# EIT_Recorder.net
KiCad netlist of a schematic drawn in EAGLE
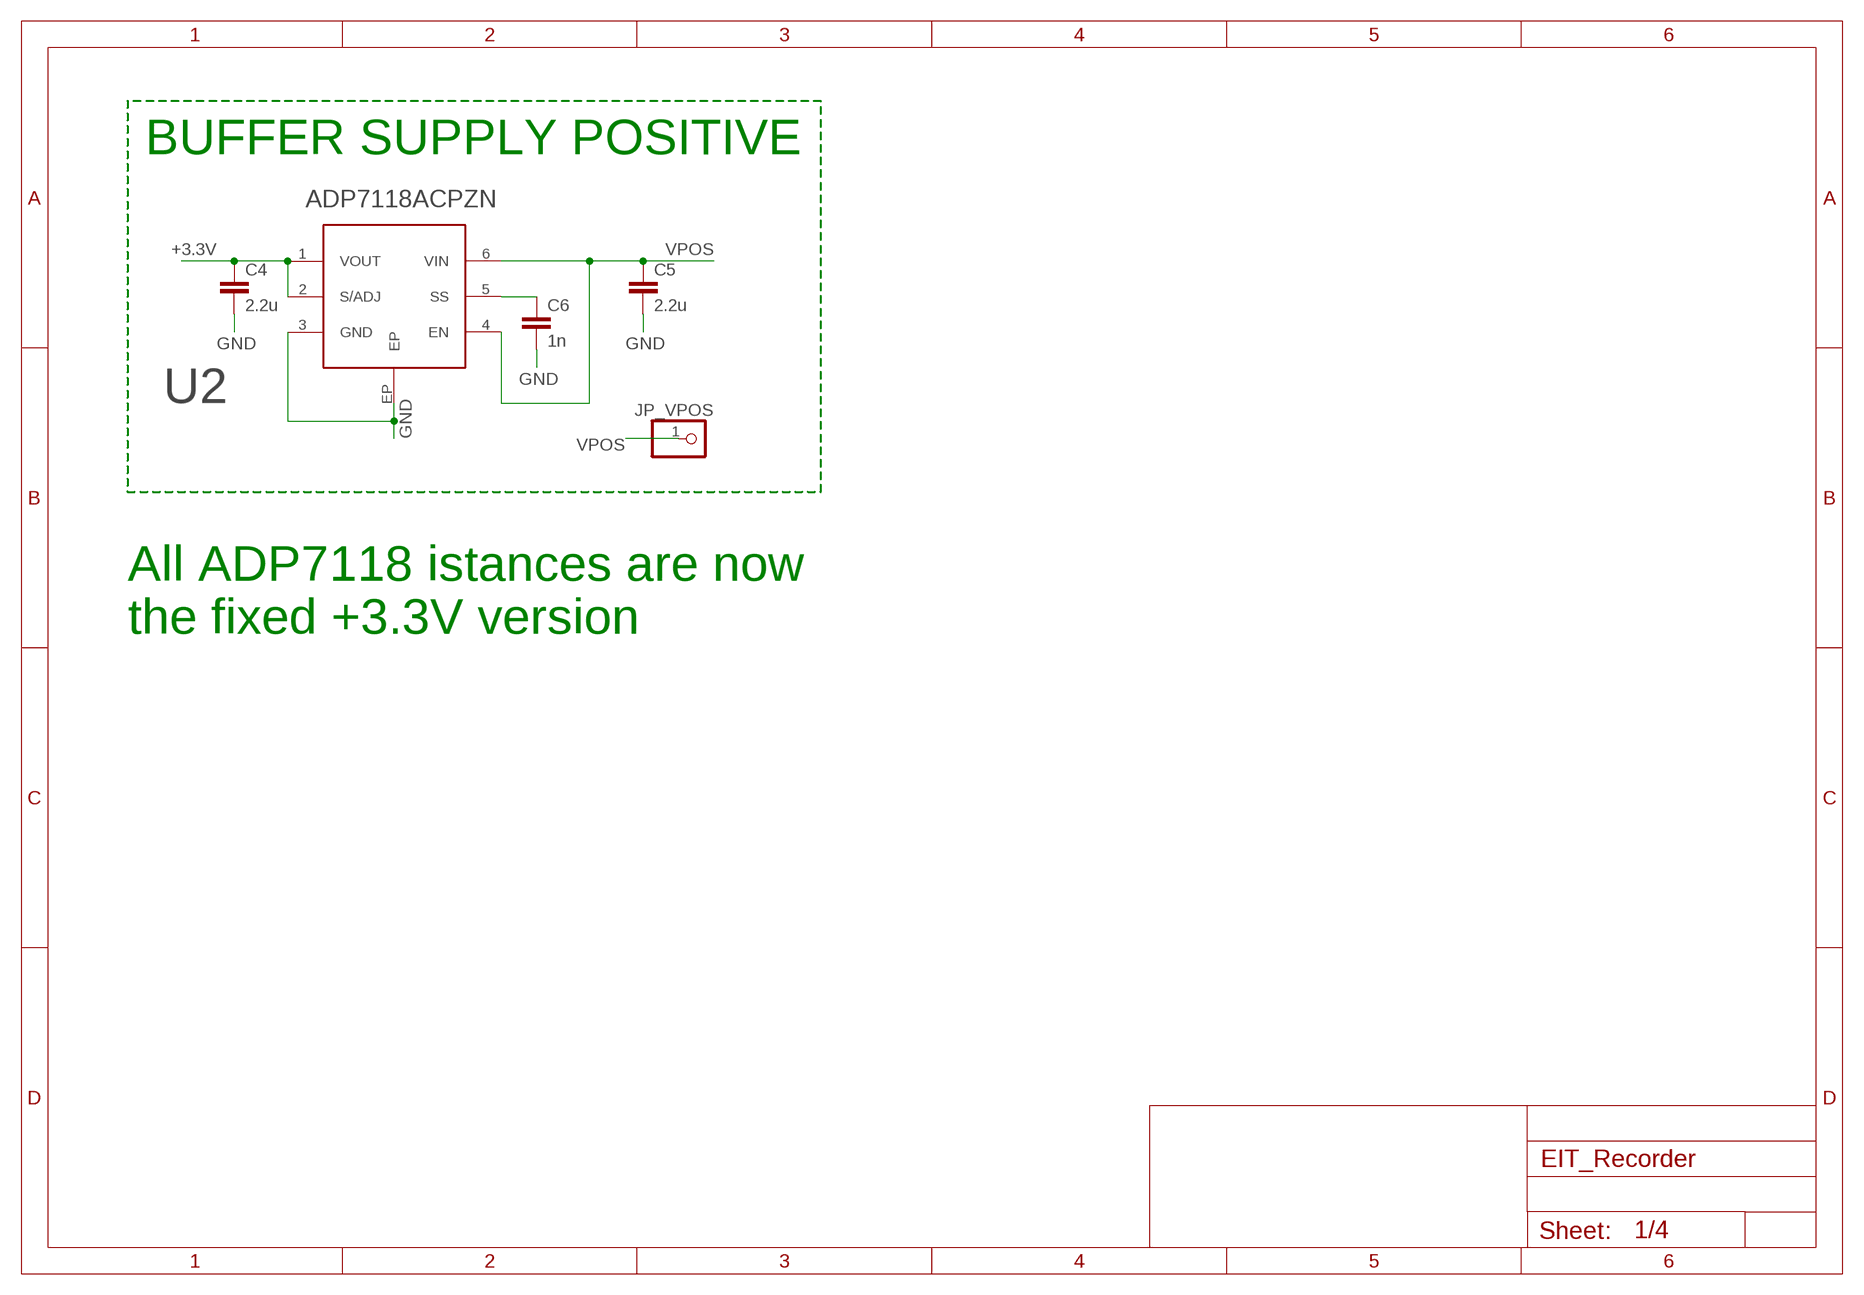
[diagram p0: schematic, sheet 1]
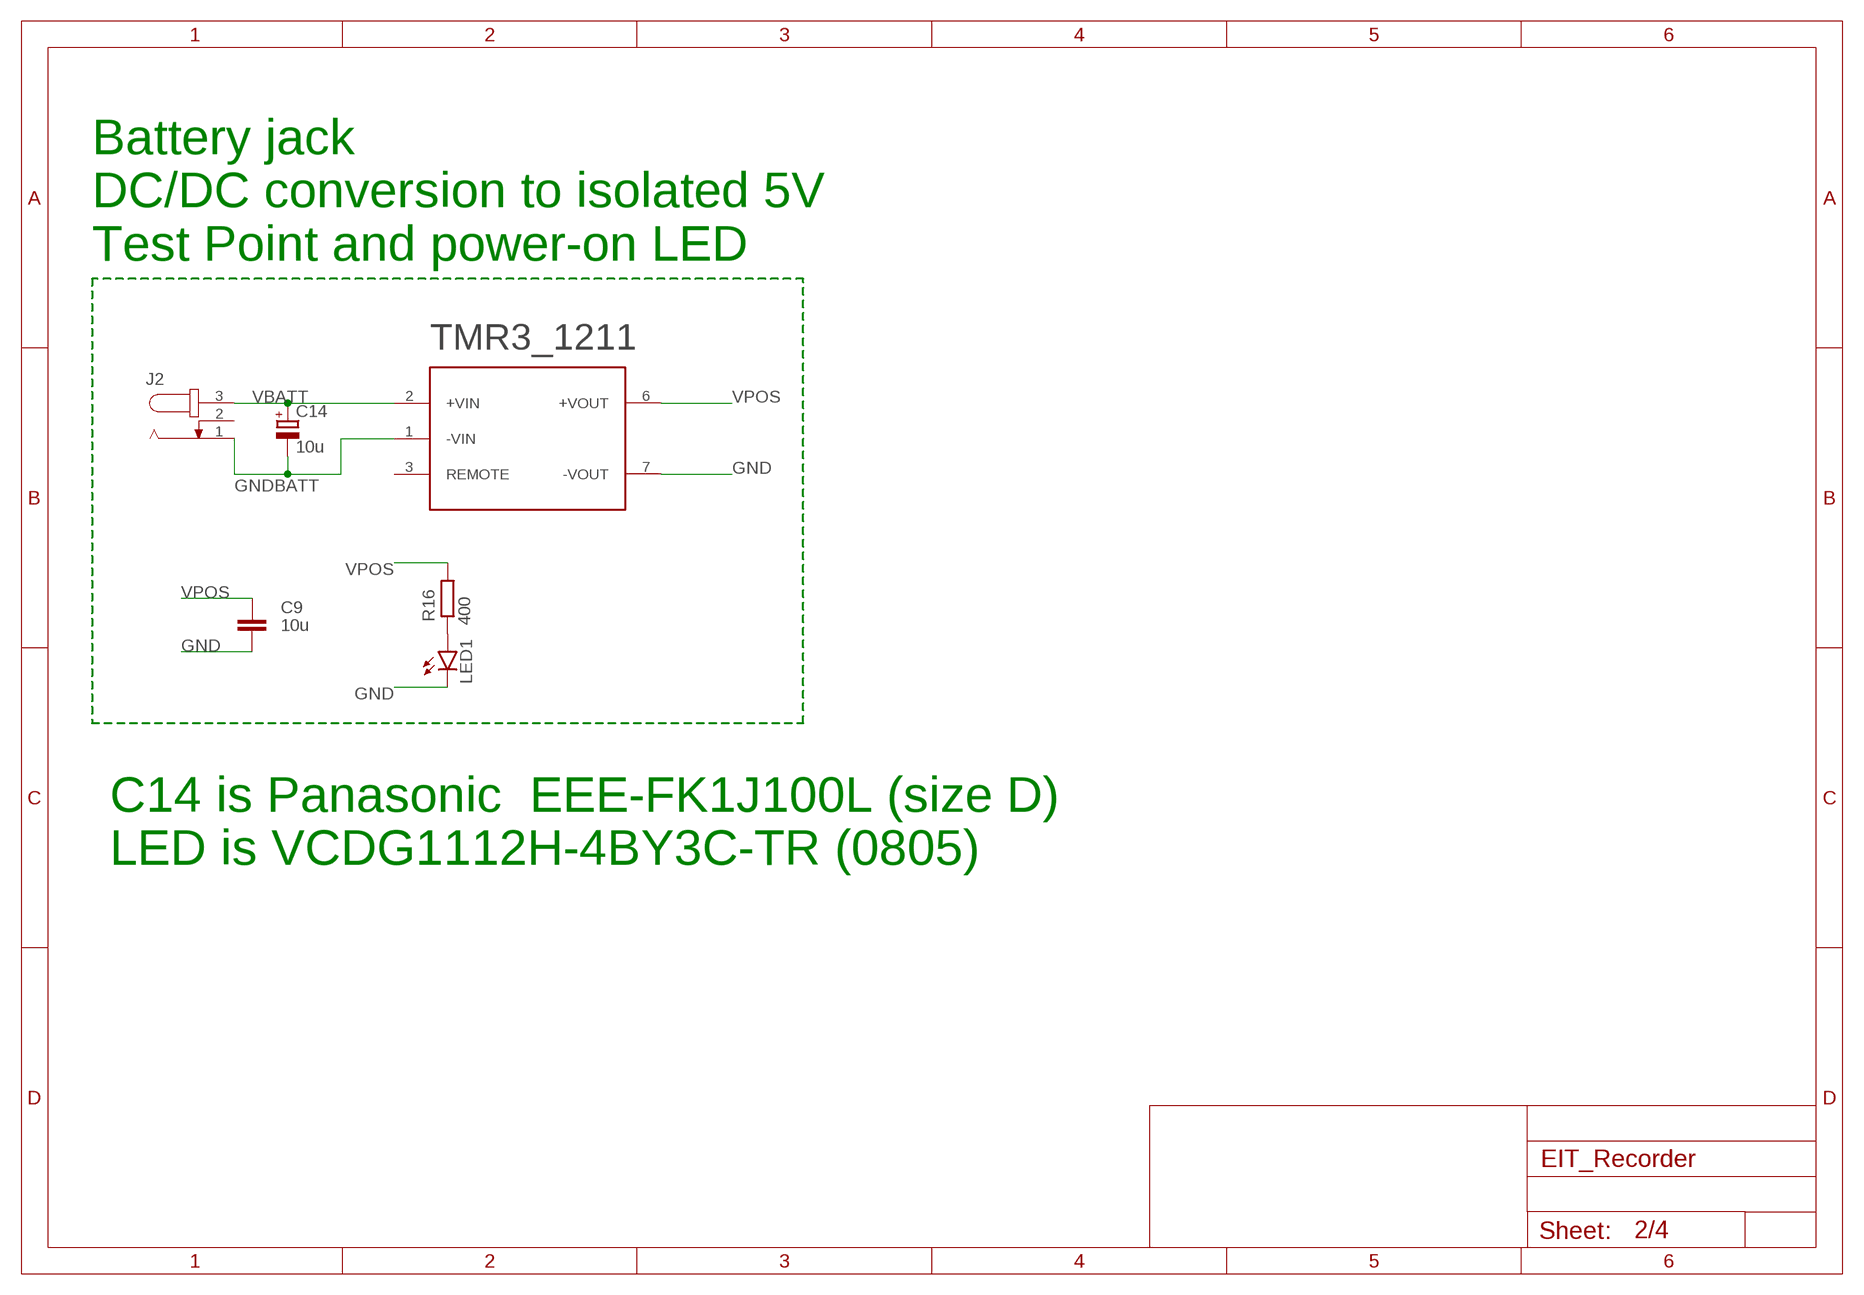
[diagram p1: schematic, sheet 2]
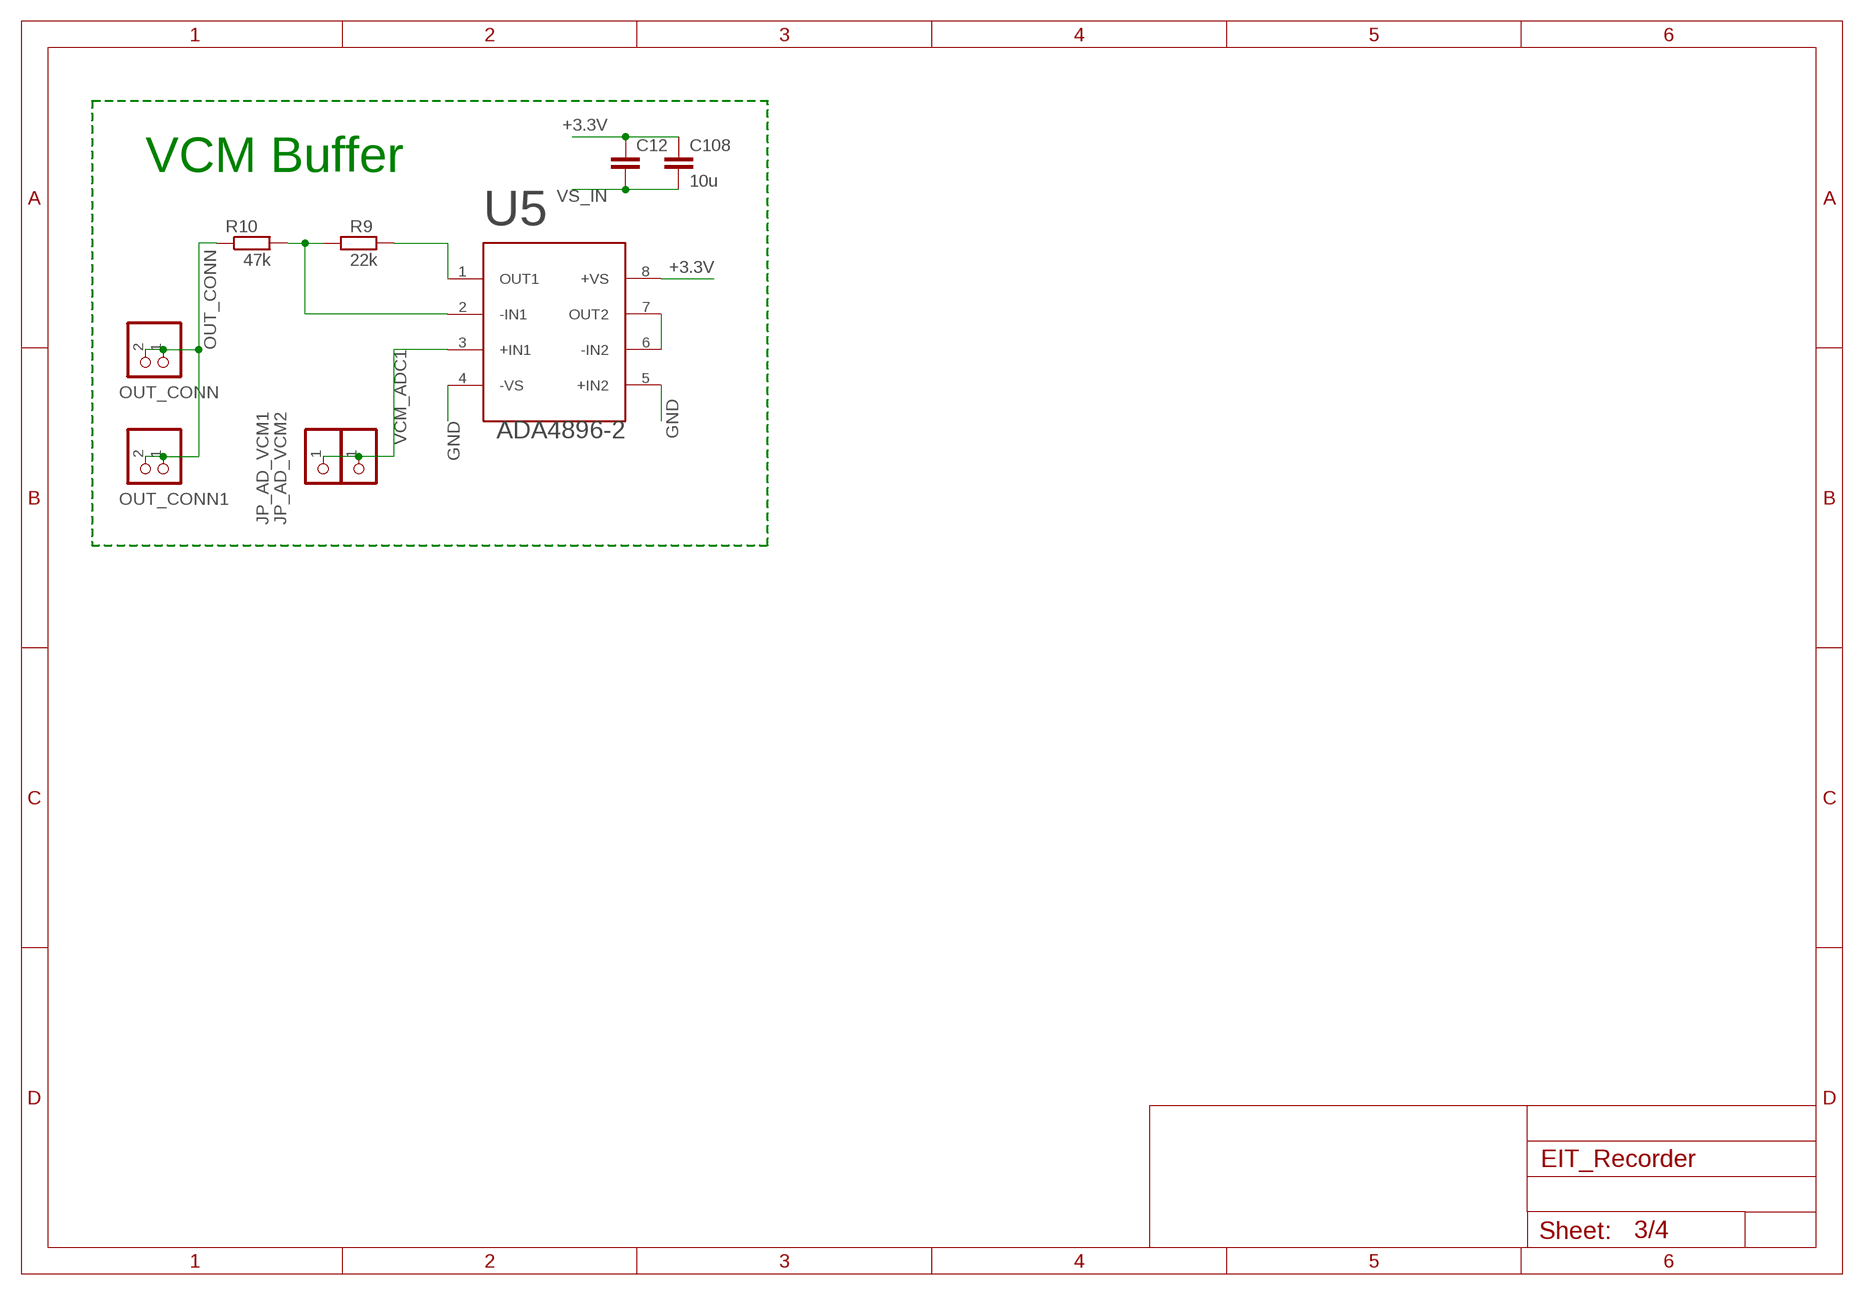
[diagram p2: schematic, sheet 3]
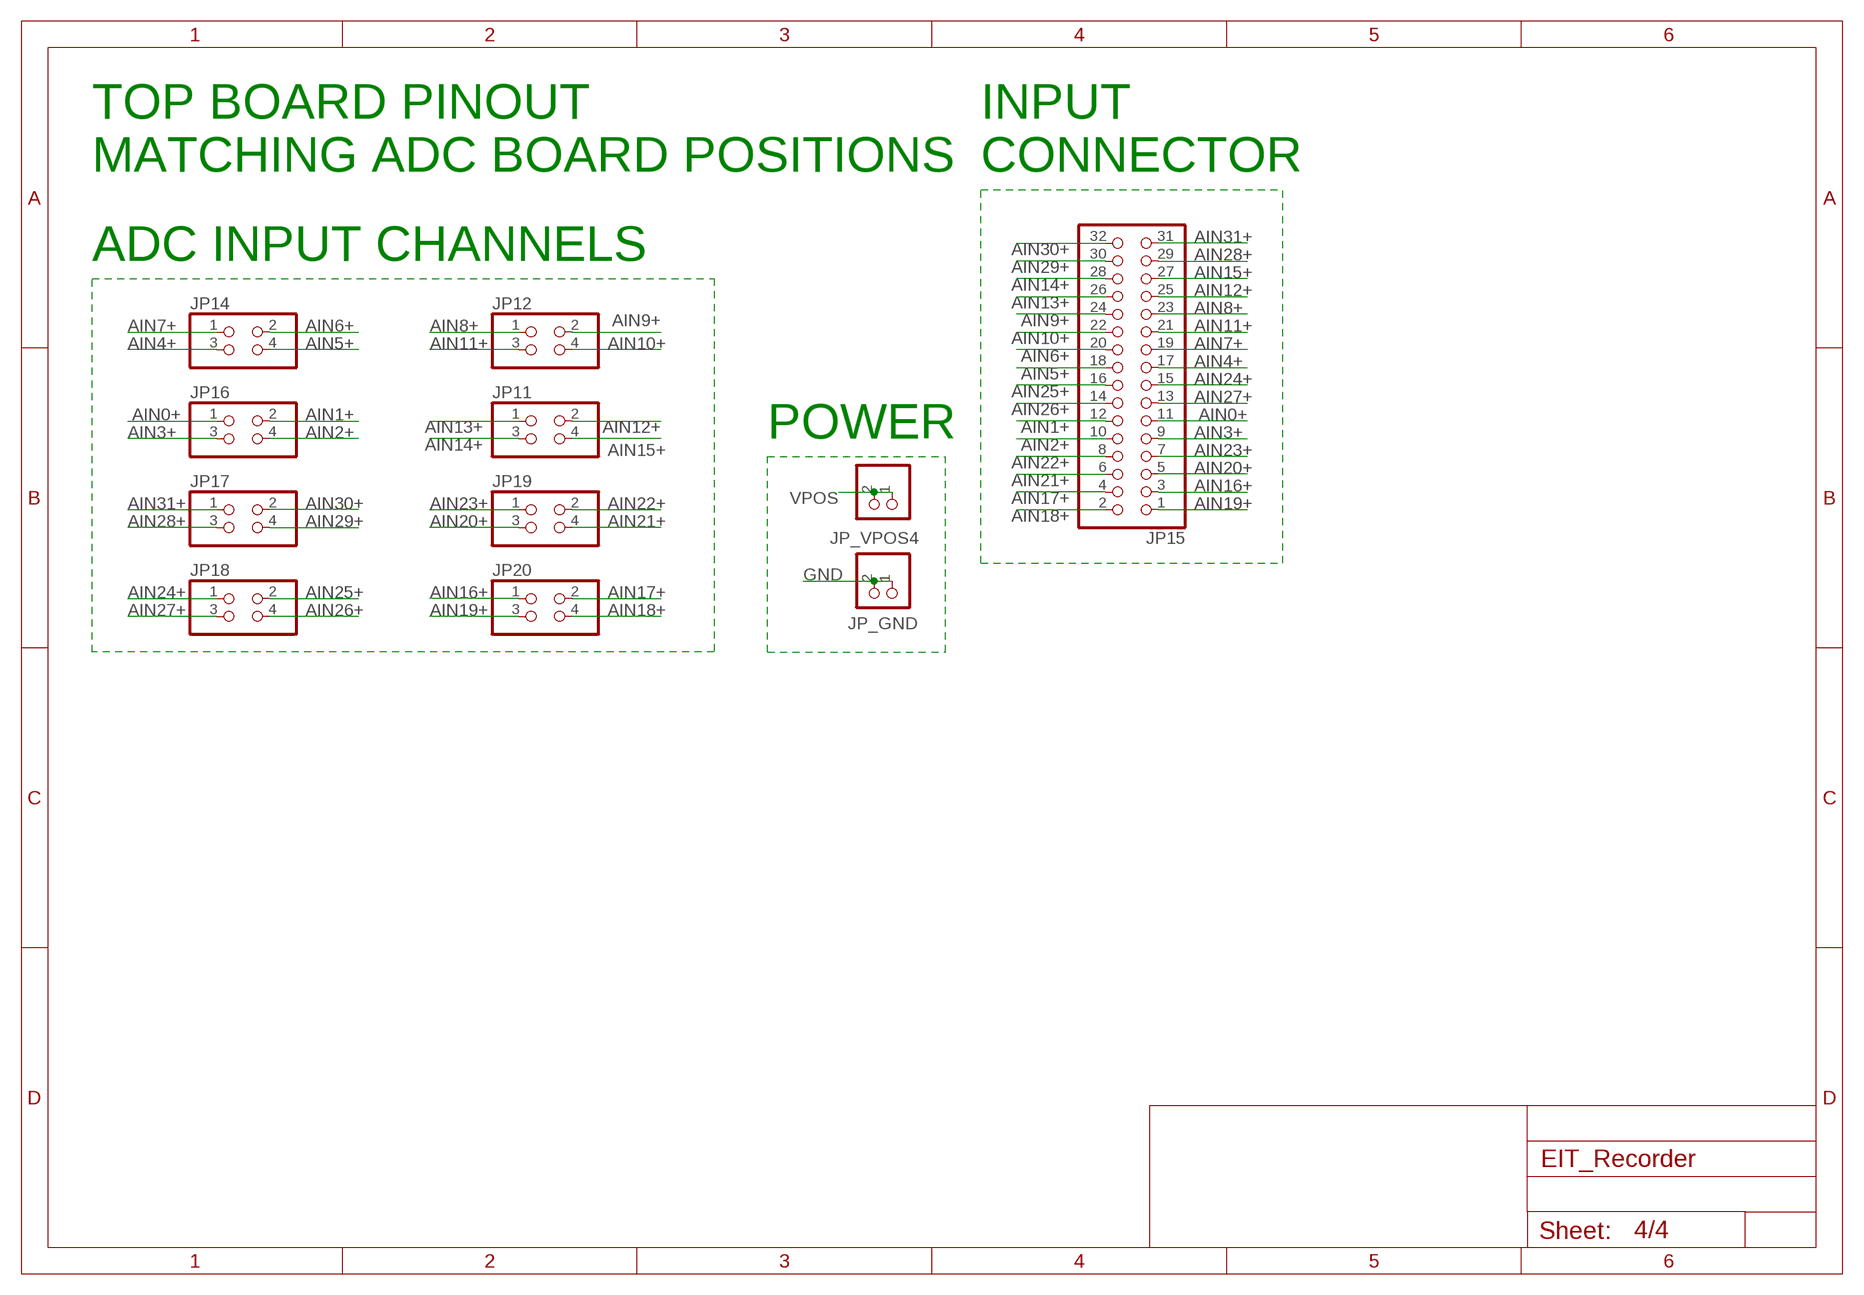
[diagram p3: schematic, sheet 4]

(export (version "E")
  (design (tool "Eeschema 10.0.6"))
  (components
    (comp (ref "C9")
      (value "10u")
      (footprint "eagle-import:C0805")
      (libsource (lib "eagle-import") (part "C0805"))
    )
    (comp (ref "C14")
      (value "10u")
      (footprint "eagle-import:PANASONIC_D")
      (libsource (lib "eagle-import") (part "CPOL-EUD"))
    )
    (comp (ref "J2")
      (value "JACK-PLUG0")
      (footprint "eagle-import:SPC4077")
      (libsource (lib "eagle-import") (part "JACK-PLUG0"))
    )
    (comp (ref "LED1")
      (value "LEDCHIP-LED0805")
      (footprint "eagle-import:CHIP-LED0805")
      (libsource (lib "eagle-import") (part "LEDCHIP-LED0805"))
    )
    (comp (ref "R16")
      (value "400")
      (footprint "eagle-import:R0805")
      (libsource (lib "eagle-import") (part "R-EU_R0805"))
    )
    (comp (ref "TMR3_1211")
      (value "TMR3_1211")
      (footprint "eagle-import:TMR3_1211")
      (libsource (lib "eagle-import") (part "TMR3_1211"))
    )
    (comp (ref "C12")
      (value "0.1u")
      (footprint "eagle-import:C0402")
      (libsource (lib "eagle-import") (part "C0402"))
    )
    (comp (ref "C108")
      (value "10u")
      (footprint "eagle-import:C0805")
      (libsource (lib "eagle-import") (part "C0805"))
    )
    (comp (ref "JP_AD_VCM1")
      (value "PINHD-1X1")
      (footprint "eagle-import:1X01")
      (libsource (lib "eagle-import") (part "PINHD-1X1"))
    )
    (comp (ref "JP_AD_VCM2")
      (value "PINHD-1X1")
      (footprint "eagle-import:1X01")
      (libsource (lib "eagle-import") (part "PINHD-1X1"))
    )
    (comp (ref "OUT_CONN")
      (value "PINHD-1X2")
      (footprint "eagle-import:1X02")
      (libsource (lib "eagle-import") (part "PINHD-1X2"))
    )
    (comp (ref "OUT_CONN1")
      (value "PINHD-1X2")
      (footprint "eagle-import:1X02")
      (libsource (lib "eagle-import") (part "PINHD-1X2"))
    )
    (comp (ref "R9")
      (value "22k")
      (footprint "eagle-import:R0603")
      (libsource (lib "eagle-import") (part "R0603"))
    )
    (comp (ref "R10")
      (value "47k")
      (footprint "eagle-import:R0603")
      (libsource (lib "eagle-import") (part "R0603"))
    )
    (comp (ref "U5")
      (value "ADA4896-2")
      (footprint "eagle-import:MSOP8_CUSTOM")
      (libsource (lib "eagle-import") (part "ADA4896-2"))
    )
    (comp (ref "JP11")
      (value "PINHD-2X2")
      (footprint "eagle-import:2X02")
      (libsource (lib "eagle-import") (part "PINHD-2X2"))
    )
    (comp (ref "JP12")
      (value "PINHD-2X2")
      (footprint "eagle-import:2X02")
      (libsource (lib "eagle-import") (part "PINHD-2X2"))
    )
    (comp (ref "JP14")
      (value "PINHD-2X2")
      (footprint "eagle-import:2X02")
      (libsource (lib "eagle-import") (part "PINHD-2X2"))
    )
    (comp (ref "JP15")
      (value "PINHD-2X16")
      (footprint "eagle-import:2X16")
      (libsource (lib "eagle-import") (part "PINHD-2X16"))
    )
    (comp (ref "JP16")
      (value "PINHD-2X2")
      (footprint "eagle-import:2X02")
      (libsource (lib "eagle-import") (part "PINHD-2X2"))
    )
    (comp (ref "JP17")
      (value "PINHD-2X2")
      (footprint "eagle-import:2X02")
      (libsource (lib "eagle-import") (part "PINHD-2X2"))
    )
    (comp (ref "JP18")
      (value "PINHD-2X2")
      (footprint "eagle-import:2X02")
      (libsource (lib "eagle-import") (part "PINHD-2X2"))
    )
    (comp (ref "JP19")
      (value "PINHD-2X2")
      (footprint "eagle-import:2X02")
      (libsource (lib "eagle-import") (part "PINHD-2X2"))
    )
    (comp (ref "JP20")
      (value "PINHD-2X2")
      (footprint "eagle-import:2X02")
      (libsource (lib "eagle-import") (part "PINHD-2X2"))
    )
    (comp (ref "JP_GND")
      (value "PINHD-1X2")
      (footprint "eagle-import:1X02")
      (libsource (lib "eagle-import") (part "PINHD-1X2"))
    )
    (comp (ref "JP_VPOS4")
      (value "PINHD-1X2")
      (footprint "eagle-import:1X02")
      (libsource (lib "eagle-import") (part "PINHD-1X2"))
    )
    (comp (ref "C4")
      (value "2.2u")
      (footprint "eagle-import:C0603")
      (libsource (lib "eagle-import") (part "C0603"))
    )
    (comp (ref "C5")
      (value "2.2u")
      (footprint "eagle-import:C0603")
      (libsource (lib "eagle-import") (part "C0603"))
    )
    (comp (ref "C6")
      (value "1n")
      (footprint "eagle-import:C0402")
      (libsource (lib "eagle-import") (part "C0402"))
    )
    (comp (ref "JP_VPOS")
      (value "PINHD-1X1")
      (footprint "eagle-import:1X01")
      (libsource (lib "eagle-import") (part "PINHD-1X1"))
    )
    (comp (ref "U2")
      (value "ADP7118ACPZN")
      (footprint "eagle-import:LFCSP6_CUSTOM")
      (libsource (lib "eagle-import") (part "ADP7118ACPZN"))
    )
  )
  (nets
    (net (code "1") (name "+3.3V") (class "Default")
      (node (ref "C108") (pin "1") (pinfunction "1_1") (pintype "passive"))
      (node (ref "C12") (pin "1") (pinfunction "1_1") (pintype "passive"))
      (node (ref "C4") (pin "1") (pinfunction "1_1") (pintype "passive"))
      (node (ref "U2") (pin "1") (pinfunction "VOUT_1") (pintype "power_in"))
      (node (ref "U2") (pin "2") (pinfunction "S/ADJ_2") (pintype "bidirectional"))
      (node (ref "U5") (pin "8") (pinfunction "+VS_8") (pintype "power_in"))
    )
    (net (code "2") (name "AIN0+") (class "Default")
      (node (ref "JP15") (pin "11") (pinfunction "11_11") (pintype "passive"))
      (node (ref "JP16") (pin "1") (pinfunction "1_1") (pintype "passive"))
    )
    (net (code "3") (name "AIN1+") (class "Default")
      (node (ref "JP15") (pin "12") (pinfunction "12_12") (pintype "passive"))
      (node (ref "JP16") (pin "2") (pinfunction "2_2") (pintype "passive"))
    )
    (net (code "4") (name "AIN2+") (class "Default")
      (node (ref "JP15") (pin "10") (pinfunction "10_10") (pintype "passive"))
      (node (ref "JP16") (pin "4") (pinfunction "4_4") (pintype "passive"))
    )
    (net (code "5") (name "AIN3+") (class "Default")
      (node (ref "JP15") (pin "9") (pinfunction "9_9") (pintype "passive"))
      (node (ref "JP16") (pin "3") (pinfunction "3_3") (pintype "passive"))
    )
    (net (code "6") (name "AIN4+") (class "Default")
      (node (ref "JP14") (pin "3") (pinfunction "3_3") (pintype "passive"))
      (node (ref "JP15") (pin "17") (pinfunction "17_17") (pintype "passive"))
    )
    (net (code "7") (name "AIN5+") (class "Default")
      (node (ref "JP14") (pin "4") (pinfunction "4_4") (pintype "passive"))
      (node (ref "JP15") (pin "18") (pinfunction "18_18") (pintype "passive"))
    )
    (net (code "8") (name "AIN6+") (class "Default")
      (node (ref "JP14") (pin "2") (pinfunction "2_2") (pintype "passive"))
      (node (ref "JP15") (pin "20") (pinfunction "20_20") (pintype "passive"))
    )
    (net (code "9") (name "AIN7+") (class "Default")
      (node (ref "JP14") (pin "1") (pinfunction "1_1") (pintype "passive"))
      (node (ref "JP15") (pin "19") (pinfunction "19_19") (pintype "passive"))
    )
    (net (code "10") (name "AIN8+") (class "Default")
      (node (ref "JP12") (pin "1") (pinfunction "1_1") (pintype "passive"))
      (node (ref "JP15") (pin "23") (pinfunction "23_23") (pintype "passive"))
    )
    (net (code "11") (name "AIN9+") (class "Default")
      (node (ref "JP12") (pin "2") (pinfunction "2_2") (pintype "passive"))
      (node (ref "JP15") (pin "24") (pinfunction "24_24") (pintype "passive"))
    )
    (net (code "12") (name "AIN10+") (class "Default")
      (node (ref "JP12") (pin "4") (pinfunction "4_4") (pintype "passive"))
      (node (ref "JP15") (pin "22") (pinfunction "22_22") (pintype "passive"))
    )
    (net (code "13") (name "AIN11+") (class "Default")
      (node (ref "JP12") (pin "3") (pinfunction "3_3") (pintype "passive"))
      (node (ref "JP15") (pin "21") (pinfunction "21_21") (pintype "passive"))
    )
    (net (code "14") (name "AIN12+") (class "Default")
      (node (ref "JP11") (pin "2") (pinfunction "2_2") (pintype "passive"))
      (node (ref "JP15") (pin "25") (pinfunction "25_25") (pintype "passive"))
    )
    (net (code "15") (name "AIN13+") (class "Default")
      (node (ref "JP11") (pin "1") (pinfunction "1_1") (pintype "passive"))
      (node (ref "JP15") (pin "26") (pinfunction "26_26") (pintype "passive"))
    )
    (net (code "16") (name "AIN14+") (class "Default")
      (node (ref "JP11") (pin "3") (pinfunction "3_3") (pintype "passive"))
      (node (ref "JP15") (pin "28") (pinfunction "28_28") (pintype "passive"))
    )
    (net (code "17") (name "AIN15+") (class "Default")
      (node (ref "JP11") (pin "4") (pinfunction "4_4") (pintype "passive"))
      (node (ref "JP15") (pin "27") (pinfunction "27_27") (pintype "passive"))
    )
    (net (code "18") (name "AIN16+") (class "Default")
      (node (ref "JP15") (pin "3") (pinfunction "3_3") (pintype "passive"))
      (node (ref "JP20") (pin "1") (pinfunction "1_1") (pintype "passive"))
    )
    (net (code "19") (name "AIN17+") (class "Default")
      (node (ref "JP15") (pin "4") (pinfunction "4_4") (pintype "passive"))
      (node (ref "JP20") (pin "2") (pinfunction "2_2") (pintype "passive"))
    )
    (net (code "20") (name "AIN18+") (class "Default")
      (node (ref "JP15") (pin "2") (pinfunction "2_2") (pintype "passive"))
      (node (ref "JP20") (pin "4") (pinfunction "4_4") (pintype "passive"))
    )
    (net (code "21") (name "AIN19+") (class "Default")
      (node (ref "JP15") (pin "1") (pinfunction "1_1") (pintype "passive"))
      (node (ref "JP20") (pin "3") (pinfunction "3_3") (pintype "passive"))
    )
    (net (code "22") (name "AIN20+") (class "Default")
      (node (ref "JP15") (pin "5") (pinfunction "5_5") (pintype "passive"))
      (node (ref "JP19") (pin "3") (pinfunction "3_3") (pintype "passive"))
    )
    (net (code "23") (name "AIN21+") (class "Default")
      (node (ref "JP15") (pin "6") (pinfunction "6_6") (pintype "passive"))
      (node (ref "JP19") (pin "4") (pinfunction "4_4") (pintype "passive"))
    )
    (net (code "24") (name "AIN22+") (class "Default")
      (node (ref "JP15") (pin "8") (pinfunction "8_8") (pintype "passive"))
      (node (ref "JP19") (pin "2") (pinfunction "2_2") (pintype "passive"))
    )
    (net (code "25") (name "AIN23+") (class "Default")
      (node (ref "JP15") (pin "7") (pinfunction "7_7") (pintype "passive"))
      (node (ref "JP19") (pin "1") (pinfunction "1_1") (pintype "passive"))
    )
    (net (code "26") (name "AIN24+") (class "Default")
      (node (ref "JP15") (pin "15") (pinfunction "15_15") (pintype "passive"))
      (node (ref "JP18") (pin "1") (pinfunction "1_1") (pintype "passive"))
    )
    (net (code "27") (name "AIN25+") (class "Default")
      (node (ref "JP15") (pin "16") (pinfunction "16_16") (pintype "passive"))
      (node (ref "JP18") (pin "2") (pinfunction "2_2") (pintype "passive"))
    )
    (net (code "28") (name "AIN26+") (class "Default")
      (node (ref "JP15") (pin "14") (pinfunction "14_14") (pintype "passive"))
      (node (ref "JP18") (pin "4") (pinfunction "4_4") (pintype "passive"))
    )
    (net (code "29") (name "AIN27+") (class "Default")
      (node (ref "JP15") (pin "13") (pinfunction "13_13") (pintype "passive"))
      (node (ref "JP18") (pin "3") (pinfunction "3_3") (pintype "passive"))
    )
    (net (code "30") (name "AIN28+") (class "Default")
      (node (ref "JP15") (pin "29") (pinfunction "29_29") (pintype "passive"))
      (node (ref "JP17") (pin "3") (pinfunction "3_3") (pintype "passive"))
    )
    (net (code "31") (name "AIN29+") (class "Default")
      (node (ref "JP15") (pin "30") (pinfunction "30_30") (pintype "passive"))
      (node (ref "JP17") (pin "4") (pinfunction "4_4") (pintype "passive"))
    )
    (net (code "32") (name "AIN30+") (class "Default")
      (node (ref "JP15") (pin "32") (pinfunction "32_32") (pintype "passive"))
      (node (ref "JP17") (pin "2") (pinfunction "2_2") (pintype "passive"))
    )
    (net (code "33") (name "AIN31+") (class "Default")
      (node (ref "JP15") (pin "31") (pinfunction "31_31") (pintype "passive"))
      (node (ref "JP17") (pin "1") (pinfunction "1_1") (pintype "passive"))
    )
    (net (code "34") (name "GND") (class "Default")
      (node (ref "C4") (pin "2") (pinfunction "2_2") (pintype "passive"))
      (node (ref "C5") (pin "2") (pinfunction "2_2") (pintype "passive"))
      (node (ref "C6") (pin "2") (pinfunction "2_2") (pintype "passive"))
      (node (ref "C9") (pin "2") (pinfunction "2_2") (pintype "passive"))
      (node (ref "JP_GND") (pin "1") (pinfunction "1_1") (pintype "passive"))
      (node (ref "JP_GND") (pin "2") (pinfunction "2_2") (pintype "passive"))
      (node (ref "LED1") (pin "C") (pinfunction "C_C") (pintype "passive"))
      (node (ref "TMR3_1211") (pin "7") (pinfunction "-VOUT_7") (pintype "passive"))
      (node (ref "U2") (pin "3") (pinfunction "GND_3") (pintype "power_in"))
      (node (ref "U2") (pin "EP") (pinfunction "EP_EP") (pintype "power_in"))
      (node (ref "U5") (pin "4") (pinfunction "-VS_4") (pintype "power_in"))
      (node (ref "U5") (pin "5") (pinfunction "+IN2_5") (pintype "input"))
    )
    (net (code "35") (name "GNDBATT") (class "Default")
      (node (ref "C14") (pin "-") (pinfunction "-_-") (pintype "passive"))
      (node (ref "J2") (pin "1") (pinfunction "1_1") (pintype "passive"))
      (node (ref "TMR3_1211") (pin "1") (pinfunction "-VIN_1") (pintype "passive"))
    )
    (net (code "36") (name "Net-(LED1-PadA)") (class "Default")
      (node (ref "LED1") (pin "A") (pinfunction "A_A") (pintype "passive"))
      (node (ref "R16") (pin "1") (pinfunction "1_1") (pintype "passive"))
    )
    (net (code "37") (name "Net-(U2-SS)") (class "Default")
      (node (ref "C6") (pin "1") (pinfunction "1_1") (pintype "passive"))
      (node (ref "U2") (pin "5") (pinfunction "SS_5") (pintype "bidirectional"))
    )
    (net (code "38") (name "Net-(U5--IN1)") (class "Default")
      (node (ref "R10") (pin "2") (pinfunction "2_2") (pintype "passive"))
      (node (ref "R9") (pin "1") (pinfunction "1_1") (pintype "passive"))
      (node (ref "U5") (pin "2") (pinfunction "-IN1_2") (pintype "input"))
    )
    (net (code "39") (name "Net-(U5--IN2)") (class "Default")
      (node (ref "U5") (pin "6") (pinfunction "-IN2_6") (pintype "input"))
      (node (ref "U5") (pin "7") (pinfunction "OUT2_7") (pintype "output"))
    )
    (net (code "40") (name "Net-(U5-OUT1)") (class "Default")
      (node (ref "R9") (pin "2") (pinfunction "2_2") (pintype "passive"))
      (node (ref "U5") (pin "1") (pinfunction "OUT1_1") (pintype "output"))
    )
    (net (code "41") (name "OUT_CONN") (class "Default")
      (node (ref "OUT_CONN") (pin "1") (pinfunction "1_1") (pintype "passive"))
      (node (ref "OUT_CONN") (pin "2") (pinfunction "2_2") (pintype "passive"))
      (node (ref "OUT_CONN1") (pin "1") (pinfunction "1_1") (pintype "passive"))
      (node (ref "OUT_CONN1") (pin "2") (pinfunction "2_2") (pintype "passive"))
      (node (ref "R10") (pin "1") (pinfunction "1_1") (pintype "passive"))
    )
    (net (code "42") (name "VBATT") (class "Default")
      (node (ref "C14") (pin "+") (pinfunction "+_+") (pintype "passive"))
      (node (ref "J2") (pin "3") (pinfunction "3_3") (pintype "passive"))
      (node (ref "TMR3_1211") (pin "2") (pinfunction "+VIN_2") (pintype "power_in"))
    )
    (net (code "43") (name "VCM_ADC1") (class "Default")
      (node (ref "JP_AD_VCM1") (pin "1") (pinfunction "1_1") (pintype "passive"))
      (node (ref "JP_AD_VCM2") (pin "1") (pinfunction "1_1") (pintype "passive"))
      (node (ref "U5") (pin "3") (pinfunction "+IN1_3") (pintype "input"))
    )
    (net (code "44") (name "VPOS") (class "Default")
      (node (ref "C5") (pin "1") (pinfunction "1_1") (pintype "passive"))
      (node (ref "C9") (pin "1") (pinfunction "1_1") (pintype "passive"))
      (node (ref "JP_VPOS") (pin "1") (pinfunction "1_1") (pintype "passive"))
      (node (ref "JP_VPOS4") (pin "1") (pinfunction "1_1") (pintype "passive"))
      (node (ref "JP_VPOS4") (pin "2") (pinfunction "2_2") (pintype "passive"))
      (node (ref "R16") (pin "2") (pinfunction "2_2") (pintype "passive"))
      (node (ref "TMR3_1211") (pin "6") (pinfunction "+VOUT_6") (pintype "power_in"))
      (node (ref "U2") (pin "4") (pinfunction "EN_4") (pintype "bidirectional"))
      (node (ref "U2") (pin "6") (pinfunction "VIN_6") (pintype "power_in"))
    )
    (net (code "45") (name "VS_IN") (class "Default")
      (node (ref "C108") (pin "2") (pinfunction "2_2") (pintype "passive"))
      (node (ref "C12") (pin "2") (pinfunction "2_2") (pintype "passive"))
    )
    (net (code "46") (name "unconnected-(J2-Pad2)") (class "Default")
      (node (ref "J2") (pin "2") (pinfunction "2_2") (pintype "passive"))
    )
    (net (code "47") (name "unconnected-(TMR3_1211-REMOTE-Pad3)") (class "Default")
      (node (ref "TMR3_1211") (pin "3") (pinfunction "REMOTE_3") (pintype "bidirectional"))
    )
  )
)
